# Main.net
KiCad netlist of a schematic drawn in Altium Designer
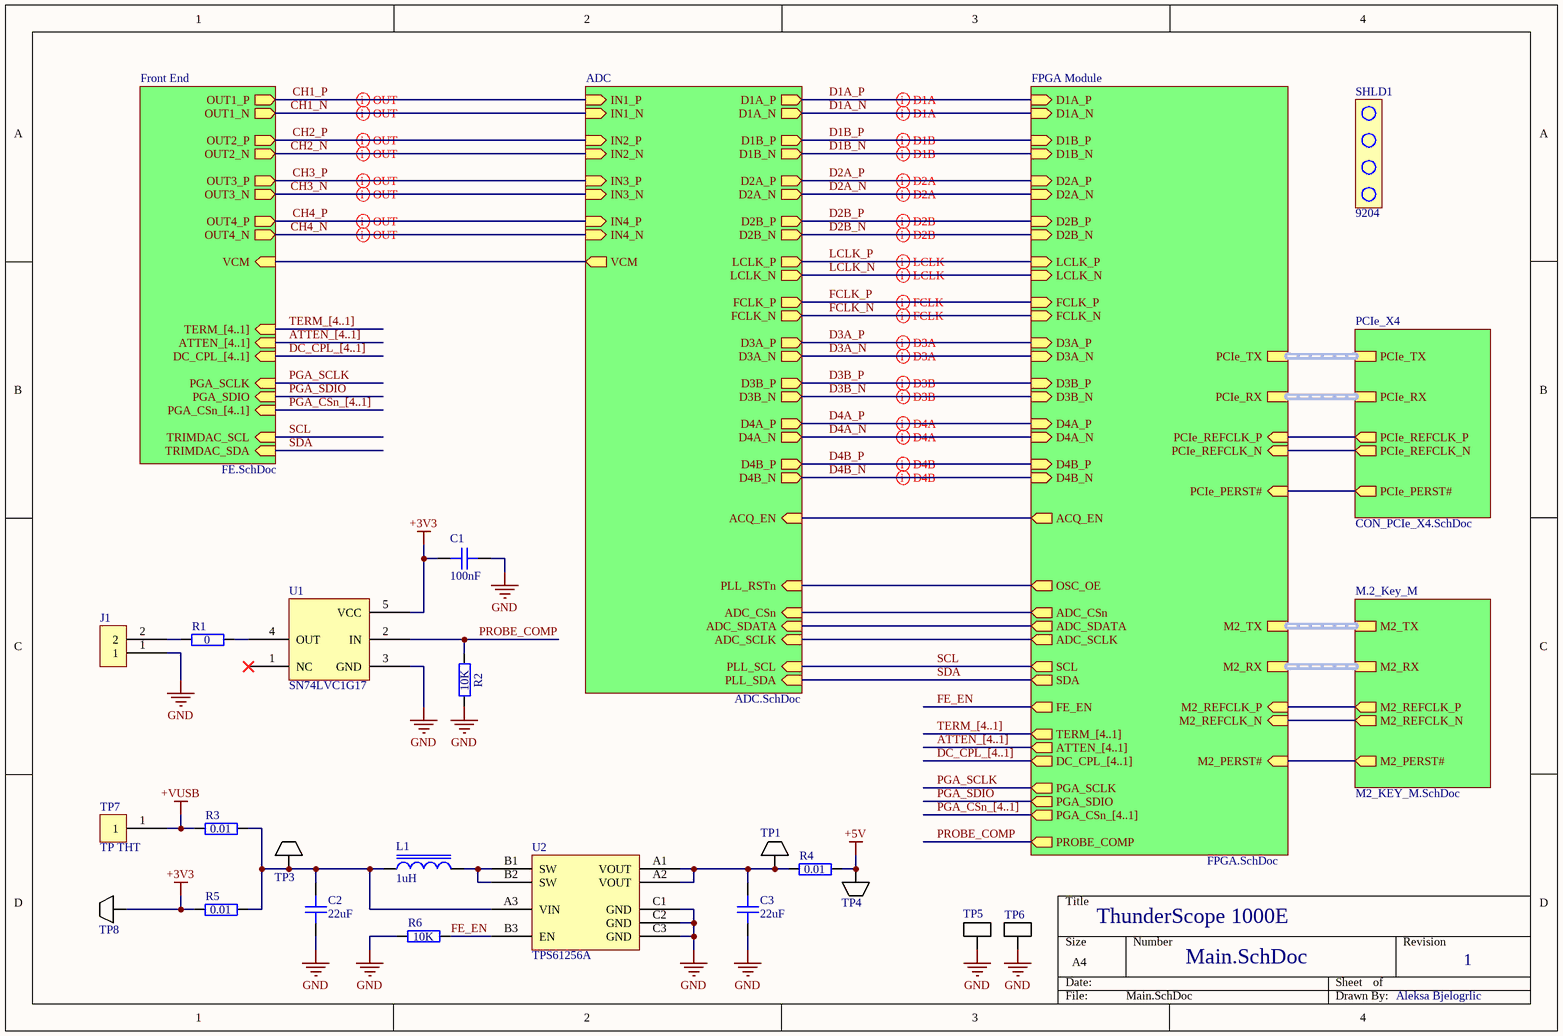
[diagram p0: Main.SchDoc]

(export (version "E")
  (design (tool "Eeschema 10.0.6"))
  (components
    (comp (ref "C1")
      (value "100nF")
      (footprint "GEN_C_0402")
      (libsource (lib "DSO") (part "CAP 100nF 16V X7R 0402"))
    )
    (comp (ref "C2")
      (value "22uF")
      (footprint "GEN_C_0805")
      (libsource (lib "DSO") (part "CAP 22uF 25V X5R 0805"))
    )
    (comp (ref "C3")
      (value "22uF")
      (footprint "GEN_C_0805")
      (libsource (lib "DSO") (part "CAP 22uF 25V X5R 0805"))
    )
    (comp (ref "J1")
      (value "TSW-101-08-F-D-RA")
      (footprint "GEN_2.54mm_1x2_Pin_TH_RA")
      (libsource (lib "DSO") (part "CONN 2.54mm 2 Pin TH RA"))
    )
    (comp (ref "L1")
      (value "1uH")
      (footprint "GEN_L_1210")
      (libsource (lib "DSO") (part "IND 1uH 3.1A 45 MOHM 1210"))
    )
    (comp (ref "R1")
      (value "0")
      (footprint "GEN_R_0402")
      (libsource (lib "DSO") (part "RES 0 OHM 1/16W 0402"))
    )
    (comp (ref "R2")
      (value "10K")
      (footprint "GEN_R_0402")
      (fields (field (name "TOLERANCE") "1%"))
      (libsource (lib "") (part "RES 10K OHM 1% 1/10W 0402_1"))
    )
    (comp (ref "R3")
      (value "0.01")
      (footprint "GEN_R_0603")
      (fields (field (name "TOLERANCE") "1%"))
      (libsource (lib "") (part "RES 0.01 OHM 1% 1/4W 0603_1"))
    )
    (comp (ref "R4")
      (value "0.01")
      (footprint "GEN_R_0603")
      (fields (field (name "TOLERANCE") "1%"))
      (libsource (lib "DSO") (part "RES 0.01 OHM 1% 1/4W 0603"))
    )
    (comp (ref "R5")
      (value "0.01")
      (footprint "GEN_R_0603")
      (fields (field (name "TOLERANCE") "1%"))
      (libsource (lib "") (part "RES 0.01 OHM 1% 1/4W 0603_1"))
    )
    (comp (ref "R6")
      (value "10K")
      (footprint "GEN_R_0402")
      (fields (field (name "TOLERANCE") "1%"))
      (libsource (lib "DSO") (part "RES 10K OHM 1% 1/10W 0402"))
    )
    (comp (ref "SHLD1") (value "9204") (libsource (lib "DSO") (part "PCIe IO Shield")))
    (comp (ref "TP1") (value "5015") (footprint "KEY_5015") (libsource (lib "DSO") (part "TP KEYSTONE 5015")))
    (comp (ref "TP3") (value "5015") (footprint "KEY_5015") (libsource (lib "DSO") (part "TP KEYSTONE 5015")))
    (comp (ref "TP4") (value "5015") (footprint "KEY_5015") (libsource (lib "DSO") (part "TP KEYSTONE 5015")))
    (comp (ref "TP5") (value "5019") (footprint "KEY_5019") (libsource (lib "DSO") (part "TP KEYSTONE 5019")))
    (comp (ref "TP6") (value "5019") (footprint "KEY_5019") (libsource (lib "DSO") (part "TP KEYSTONE 5019")))
    (comp (ref "TP7") (value "TP THT") (footprint "GEN_1_Pin_TH_TP") (libsource (lib "DSO") (part "TP THT")))
    (comp (ref "TP8") (value "5015") (footprint "KEY_5015") (libsource (lib "DSO") (part "TP KEYSTONE 5015")))
    (comp (ref "U1")
      (value "SN74LVC1G17")
      (footprint "GEN_SC-70-5")
      (libsource (lib "DSO") (part "IC BUFFER SN74LVC1G17"))
    )
    (comp (ref "U2")
      (value "TPS61256A")
      (footprint "TI_DSBGA_YFF0009")
      (libsource (lib "DSO") (part "IC BOOST TPS61256A"))
    )
  )
  (nets
    (net (code "17") (name "+3V3") (class "Default")
      (node (ref "C1") (pin "1") (pinfunction "1_1") (pintype "passive"))
      (node (ref "R5") (pin "2") (pinfunction "2_2") (pintype "passive"))
      (node (ref "TP8") (pin "1") (pinfunction "1_1") (pintype "passive"))
      (node (ref "U1") (pin "5") (pinfunction "VCC_5") (pintype "passive"))
    )
    (net (code "18") (name "+5V") (class "Default")
      (node (ref "R4") (pin "2") (pinfunction "2_2") (pintype "passive"))
      (node (ref "TP4") (pin "1") (pinfunction "1_1") (pintype "passive"))
    )
    (net (code "19") (name "+VUSB") (class "Default")
      (node (ref "R3") (pin "2") (pinfunction "2_2") (pintype "passive"))
      (node (ref "TP7") (pin "1") (pinfunction "1_1") (pintype "passive"))
    )
    (net (code "52") (name "/FE_EN") (class "Default")
      (node (ref "R6") (pin "1") (pinfunction "1_1") (pintype "passive"))
      (node (ref "U2") (pin "B3") (pinfunction "EN_B3") (pintype "passive"))
    )
    (net (code "69") (name "/PROBE_COMP") (class "Default")
      (node (ref "R2") (pin "2") (pinfunction "2_2") (pintype "passive"))
      (node (ref "U1") (pin "2") (pinfunction "IN_2") (pintype "passive"))
    )
    (net (code "74") (name "GND") (class "Default")
      (node (ref "C1") (pin "2") (pinfunction "2_2") (pintype "passive"))
      (node (ref "C2") (pin "1") (pinfunction "1_1") (pintype "passive"))
      (node (ref "C3") (pin "1") (pinfunction "1_1") (pintype "passive"))
      (node (ref "J1") (pin "1") (pinfunction "1_1") (pintype "passive"))
      (node (ref "R2") (pin "1") (pinfunction "1_1") (pintype "passive"))
      (node (ref "R6") (pin "2") (pinfunction "2_2") (pintype "passive"))
      (node (ref "TP5") (pin "1") (pinfunction "1_1") (pintype "passive"))
      (node (ref "TP6") (pin "1") (pinfunction "1_1") (pintype "passive"))
      (node (ref "U1") (pin "3") (pinfunction "GND_3") (pintype "passive"))
      (node (ref "U2") (pin "C1") (pinfunction "GND_C1") (pintype "passive"))
      (node (ref "U2") (pin "C2") (pinfunction "GND_C2") (pintype "passive"))
      (node (ref "U2") (pin "C3") (pinfunction "GND_C3") (pintype "passive"))
    )
    (net (code "75") (name "Net-(C3-Pad2)") (class "Default")
      (node (ref "C3") (pin "2") (pinfunction "2_2") (pintype "passive"))
      (node (ref "R4") (pin "1") (pinfunction "1_1") (pintype "passive"))
      (node (ref "TP1") (pin "1") (pinfunction "1_1") (pintype "passive"))
      (node (ref "U2") (pin "A1") (pinfunction "VOUT_A1") (pintype "passive"))
      (node (ref "U2") (pin "A2") (pinfunction "VOUT_A2") (pintype "passive"))
    )
    (net (code "76") (name "Net-(J1-Pad2)") (class "Default")
      (node (ref "J1") (pin "2") (pinfunction "2_2") (pintype "passive"))
      (node (ref "R1") (pin "1") (pinfunction "1_1") (pintype "passive"))
    )
    (net (code "77") (name "Net-(L1-Pad2)") (class "Default")
      (node (ref "L1") (pin "2") (pinfunction "2_2") (pintype "passive"))
      (node (ref "U2") (pin "B1") (pinfunction "SW_B1") (pintype "passive"))
      (node (ref "U2") (pin "B2") (pinfunction "SW_B2") (pintype "passive"))
    )
    (net (code "78") (name "Net-(U1-OUT)") (class "Default")
      (node (ref "R1") (pin "2") (pinfunction "2_2") (pintype "passive"))
      (node (ref "U1") (pin "4") (pinfunction "OUT_4") (pintype "passive"))
    )
    (net (code "79") (name "Net-(U2-VIN)") (class "Default")
      (node (ref "C2") (pin "2") (pinfunction "2_2") (pintype "passive"))
      (node (ref "L1") (pin "1") (pinfunction "1_1") (pintype "passive"))
      (node (ref "R3") (pin "1") (pinfunction "1_1") (pintype "passive"))
      (node (ref "R5") (pin "1") (pinfunction "1_1") (pintype "passive"))
      (node (ref "TP3") (pin "1") (pinfunction "1_1") (pintype "passive"))
      (node (ref "U2") (pin "A3") (pinfunction "VIN_A3") (pintype "passive"))
    )
    (net (code "80") (name "unconnected-(U1-NC-Pad1)") (class "Default")
      (node (ref "U1") (pin "1") (pinfunction "NC_1") (pintype "passive+no_connect"))
    )
  )
)
